# BrainA2-A-11Nov2014.net
KiCad netlist of a schematic drawn in EAGLE
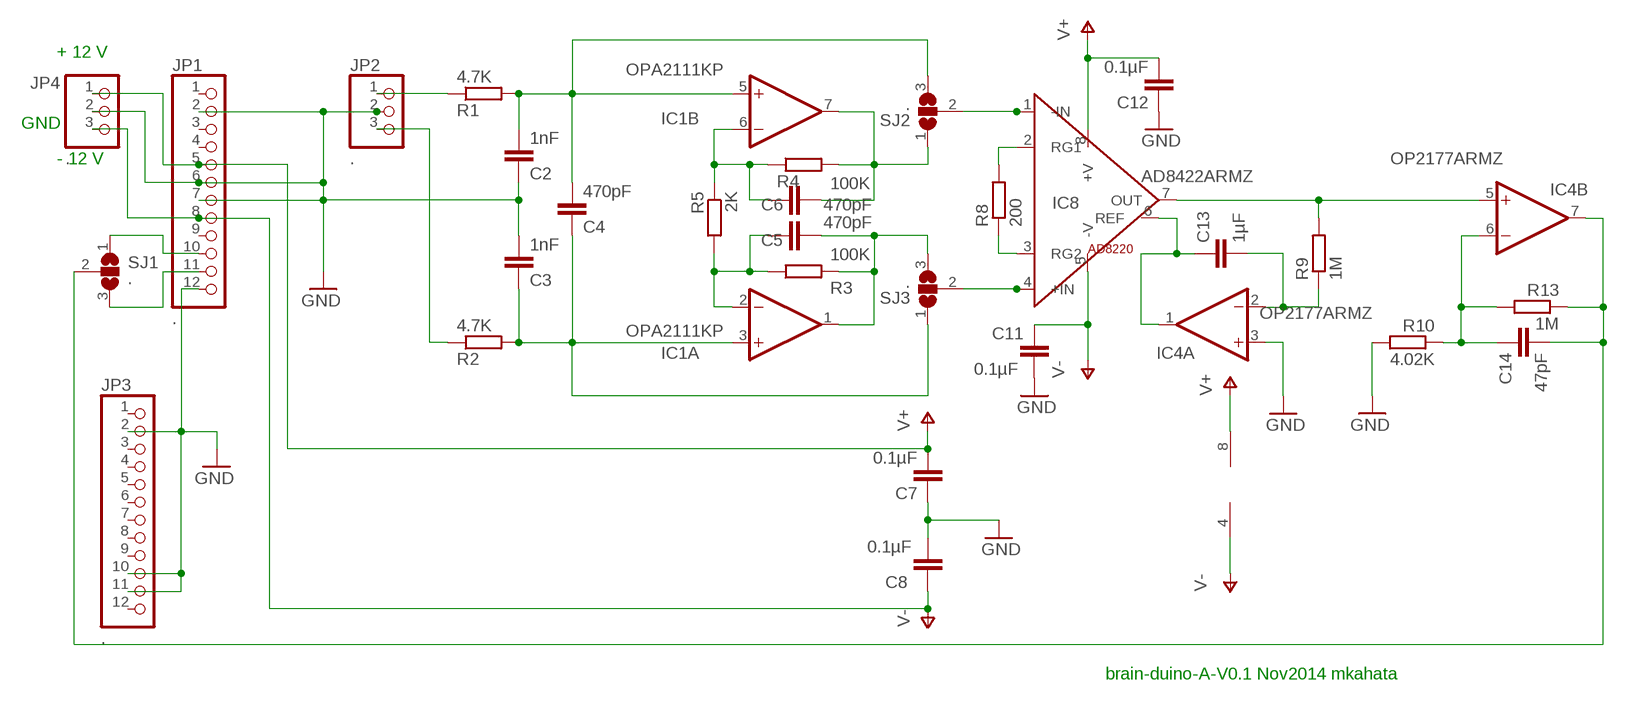
[diagram p0: schematic, sheet 1]

(export (version "E")
  (design (tool "Eeschema 10.0.6"))
  (components
    (comp (ref "C2")
      (value "1nF")
      (footprint "eagle-import:C0603")
      (libsource (lib "eagle-import") (part "C-EUC0603"))
    )
    (comp (ref "C3")
      (value "1nF")
      (footprint "eagle-import:C0603")
      (libsource (lib "eagle-import") (part "C-EUC0603"))
    )
    (comp (ref "C4")
      (value "470pF")
      (footprint "eagle-import:C0603")
      (libsource (lib "eagle-import") (part "C-EUC0603"))
    )
    (comp (ref "C5")
      (value "470pF")
      (footprint "eagle-import:C0603")
      (libsource (lib "eagle-import") (part "C-EUC0603"))
    )
    (comp (ref "C6")
      (value "470pF")
      (footprint "eagle-import:C0603")
      (libsource (lib "eagle-import") (part "C-EUC0603"))
    )
    (comp (ref "C7")
      (value "0.1µF")
      (footprint "eagle-import:C0603")
      (libsource (lib "eagle-import") (part "C-EUC0603"))
    )
    (comp (ref "C8")
      (value "0.1µF")
      (footprint "eagle-import:C0603")
      (libsource (lib "eagle-import") (part "C-EUC0603"))
    )
    (comp (ref "C11")
      (value "0.1µF")
      (footprint "eagle-import:C0603")
      (libsource (lib "eagle-import") (part "C-EUC0603"))
    )
    (comp (ref "C12")
      (value "0.1µF")
      (footprint "eagle-import:C0603")
      (libsource (lib "eagle-import") (part "C-EUC0603"))
    )
    (comp (ref "C13")
      (value "1µF")
      (footprint "eagle-import:C0603")
      (libsource (lib "eagle-import") (part "C-EUC0603"))
    )
    (comp (ref "C14")
      (value "47pF")
      (footprint "eagle-import:C0603")
      (libsource (lib "eagle-import") (part "C-EUC0603"))
    )
    (comp (ref "IC1")
      (value "OPA2111KP")
      (footprint "eagle-import:DIL08")
      (libsource (lib "eagle-import") (part "OPA2111P"))
    )
    (comp (ref "IC4")
      (value "OP2177ARMZ")
      (footprint "eagle-import:MSOP08")
      (libsource (lib "eagle-import") (part "OP1277RM"))
    )
    (comp (ref "IC8")
      (value "AD8422ARMZ")
      (footprint "eagle-import:AD8220")
      (libsource (lib "eagle-import") (part "AD8220"))
    )
    (comp (ref "JP1")
      (value ".")
      (footprint "eagle-import:1X12")
      (libsource (lib "eagle-import") (part "PINHD-1X12"))
    )
    (comp (ref "JP2")
      (value ".")
      (footprint "eagle-import:1X03")
      (libsource (lib "eagle-import") (part "PINHD-1X3"))
    )
    (comp (ref "JP3")
      (value ".")
      (footprint "eagle-import:1X12")
      (libsource (lib "eagle-import") (part "PINHD-1X12"))
    )
    (comp (ref "JP4")
      (value ".")
      (footprint "eagle-import:1X03")
      (libsource (lib "eagle-import") (part "PINHD-1X3"))
    )
    (comp (ref "R1")
      (value "4.7K")
      (footprint "eagle-import:R0603")
      (libsource (lib "eagle-import") (part "R-EU_R0603"))
    )
    (comp (ref "R2")
      (value "4.7K")
      (footprint "eagle-import:R0603")
      (libsource (lib "eagle-import") (part "R-EU_R0603"))
    )
    (comp (ref "R3")
      (value "100K")
      (footprint "eagle-import:R0603")
      (libsource (lib "eagle-import") (part "R-EU_R0603"))
    )
    (comp (ref "R4")
      (value "100K")
      (footprint "eagle-import:R0603")
      (libsource (lib "eagle-import") (part "R-EU_R0603"))
    )
    (comp (ref "R5")
      (value "2K")
      (footprint "eagle-import:R0603")
      (libsource (lib "eagle-import") (part "R-EU_R0603"))
    )
    (comp (ref "R8")
      (value "200")
      (footprint "eagle-import:R0603")
      (libsource (lib "eagle-import") (part "R-EU_R0603"))
    )
    (comp (ref "R9")
      (value "1M")
      (footprint "eagle-import:R0603")
      (libsource (lib "eagle-import") (part "R-EU_R0603"))
    )
    (comp (ref "R10")
      (value "4.02K")
      (footprint "eagle-import:R0603")
      (libsource (lib "eagle-import") (part "R-EU_R0603"))
    )
    (comp (ref "R13")
      (value "1M")
      (footprint "eagle-import:R0603")
      (libsource (lib "eagle-import") (part "R-EU_R0603"))
    )
    (comp (ref "SJ1")
      (value ".")
      (footprint "eagle-import:SJ_2")
      (libsource (lib "eagle-import") (part "SJ2W"))
    )
    (comp (ref "SJ2")
      (value ".")
      (footprint "eagle-import:SJ_2")
      (libsource (lib "eagle-import") (part "SJ2W"))
    )
    (comp (ref "SJ3")
      (value ".")
      (footprint "eagle-import:SJ_2")
      (libsource (lib "eagle-import") (part "SJ2W"))
    )
  )
  (nets
    (net (code "1") (name "GND") (class "Default")
      (node (ref "C11") (pin "2") (pinfunction "2_2") (pintype "passive"))
      (node (ref "C12") (pin "1") (pinfunction "1_1") (pintype "passive"))
      (node (ref "C2") (pin "1") (pinfunction "1_1") (pintype "passive"))
      (node (ref "C3") (pin "2") (pinfunction "2_2") (pintype "passive"))
      (node (ref "C7") (pin "1") (pinfunction "1_1") (pintype "passive"))
      (node (ref "C8") (pin "2") (pinfunction "2_2") (pintype "passive"))
      (node (ref "IC4") (pin "3") (pinfunction "+IN_3") (pintype "input"))
      (node (ref "JP1") (pin "12") (pinfunction "12_12") (pintype "passive"))
      (node (ref "JP1") (pin "2") (pinfunction "2_2") (pintype "passive"))
      (node (ref "JP1") (pin "6") (pinfunction "6_6") (pintype "passive"))
      (node (ref "JP1") (pin "7") (pinfunction "7_7") (pintype "passive"))
      (node (ref "JP2") (pin "2") (pinfunction "2_2") (pintype "passive"))
      (node (ref "JP3") (pin "10") (pinfunction "10_10") (pintype "passive"))
      (node (ref "JP3") (pin "11") (pinfunction "11_11") (pintype "passive"))
      (node (ref "JP3") (pin "2") (pinfunction "2_2") (pintype "passive"))
      (node (ref "JP4") (pin "2") (pinfunction "2_2") (pintype "passive"))
      (node (ref "R10") (pin "2") (pinfunction "2_2") (pintype "passive"))
    )
    (net (code "2") (name "Net-(IC1A-+IN)") (class "Default")
      (node (ref "C3") (pin "1") (pinfunction "1_1") (pintype "passive"))
      (node (ref "C4") (pin "1") (pinfunction "1_1") (pintype "passive"))
      (node (ref "IC1") (pin "3") (pinfunction "+IN_3") (pintype "input"))
      (node (ref "R2") (pin "2") (pinfunction "2_2") (pintype "passive"))
      (node (ref "SJ3") (pin "1") (pinfunction "1_1") (pintype "passive"))
    )
    (net (code "3") (name "Net-(IC1A--IN)") (class "Default")
      (node (ref "C5") (pin "1") (pinfunction "1_1") (pintype "passive"))
      (node (ref "IC1") (pin "2") (pinfunction "-IN_2") (pintype "input"))
      (node (ref "R3") (pin "1") (pinfunction "1_1") (pintype "passive"))
      (node (ref "R5") (pin "2") (pinfunction "2_2") (pintype "passive"))
    )
    (net (code "4") (name "Net-(IC1A-OUT)") (class "Default")
      (node (ref "C5") (pin "2") (pinfunction "2_2") (pintype "passive"))
      (node (ref "IC1") (pin "1") (pinfunction "OUT_1") (pintype "output"))
      (node (ref "R3") (pin "2") (pinfunction "2_2") (pintype "passive"))
      (node (ref "SJ3") (pin "3") (pinfunction "3_3") (pintype "passive"))
    )
    (net (code "5") (name "Net-(IC1B-+IN)") (class "Default")
      (node (ref "C2") (pin "2") (pinfunction "2_2") (pintype "passive"))
      (node (ref "C4") (pin "2") (pinfunction "2_2") (pintype "passive"))
      (node (ref "IC1") (pin "5") (pinfunction "+IN_5") (pintype "input"))
      (node (ref "R1") (pin "2") (pinfunction "2_2") (pintype "passive"))
      (node (ref "SJ2") (pin "3") (pinfunction "3_3") (pintype "passive"))
    )
    (net (code "6") (name "Net-(IC1B--IN)") (class "Default")
      (node (ref "C6") (pin "1") (pinfunction "1_1") (pintype "passive"))
      (node (ref "IC1") (pin "6") (pinfunction "-IN_6") (pintype "input"))
      (node (ref "R4") (pin "1") (pinfunction "1_1") (pintype "passive"))
      (node (ref "R5") (pin "1") (pinfunction "1_1") (pintype "passive"))
    )
    (net (code "7") (name "Net-(IC1B-OUT)") (class "Default")
      (node (ref "C6") (pin "2") (pinfunction "2_2") (pintype "passive"))
      (node (ref "IC1") (pin "7") (pinfunction "OUT_7") (pintype "output"))
      (node (ref "R4") (pin "2") (pinfunction "2_2") (pintype "passive"))
      (node (ref "SJ2") (pin "1") (pinfunction "1_1") (pintype "passive"))
    )
    (net (code "8") (name "Net-(IC4A--IN)") (class "Default")
      (node (ref "C13") (pin "2") (pinfunction "2_2") (pintype "passive"))
      (node (ref "IC4") (pin "2") (pinfunction "-IN_2") (pintype "input"))
      (node (ref "R9") (pin "1") (pinfunction "1_1") (pintype "passive"))
    )
    (net (code "9") (name "Net-(IC4A-OUT)") (class "Default")
      (node (ref "C13") (pin "1") (pinfunction "1_1") (pintype "passive"))
      (node (ref "IC4") (pin "1") (pinfunction "OUT_1") (pintype "output"))
      (node (ref "IC8") (pin "6") (pinfunction "REF_6") (pintype "input"))
    )
    (net (code "10") (name "Net-(IC4B-+IN)") (class "Default")
      (node (ref "IC4") (pin "5") (pinfunction "+IN_5") (pintype "input"))
      (node (ref "IC8") (pin "7") (pinfunction "OUT_7") (pintype "input"))
      (node (ref "R9") (pin "2") (pinfunction "2_2") (pintype "passive"))
    )
    (net (code "11") (name "Net-(IC4B--IN)") (class "Default")
      (node (ref "C14") (pin "1") (pinfunction "1_1") (pintype "passive"))
      (node (ref "IC4") (pin "6") (pinfunction "-IN_6") (pintype "input"))
      (node (ref "R10") (pin "1") (pinfunction "1_1") (pintype "passive"))
      (node (ref "R13") (pin "2") (pinfunction "2_2") (pintype "passive"))
    )
    (net (code "12") (name "Net-(IC4B-OUT)") (class "Default")
      (node (ref "C14") (pin "2") (pinfunction "2_2") (pintype "passive"))
      (node (ref "IC4") (pin "7") (pinfunction "OUT_7") (pintype "output"))
      (node (ref "R13") (pin "1") (pinfunction "1_1") (pintype "passive"))
      (node (ref "SJ1") (pin "2") (pinfunction "2_2") (pintype "passive"))
    )
    (net (code "13") (name "Net-(IC8-+IN)") (class "Default")
      (node (ref "IC8") (pin "4") (pinfunction "+IN_4") (pintype "passive"))
      (node (ref "SJ3") (pin "2") (pinfunction "2_2") (pintype "passive"))
    )
    (net (code "14") (name "Net-(IC8--IN)") (class "Default")
      (node (ref "IC8") (pin "1") (pinfunction "-IN_1") (pintype "input"))
      (node (ref "SJ2") (pin "2") (pinfunction "2_2") (pintype "passive"))
    )
    (net (code "15") (name "Net-(IC8-RG1)") (class "Default")
      (node (ref "IC8") (pin "2") (pinfunction "RG1_2") (pintype "input"))
      (node (ref "R8") (pin "2") (pinfunction "2_2") (pintype "passive"))
    )
    (net (code "16") (name "Net-(IC8-RG2)") (class "Default")
      (node (ref "IC8") (pin "3") (pinfunction "RG2_3") (pintype "input"))
      (node (ref "R8") (pin "1") (pinfunction "1_1") (pintype "passive"))
    )
    (net (code "17") (name "Net-(JP1-Pad10)") (class "Default")
      (node (ref "JP1") (pin "10") (pinfunction "10_10") (pintype "passive"))
      (node (ref "SJ1") (pin "1") (pinfunction "1_1") (pintype "passive"))
    )
    (net (code "18") (name "Net-(JP1-Pad11)") (class "Default")
      (node (ref "JP1") (pin "11") (pinfunction "11_11") (pintype "passive"))
      (node (ref "SJ1") (pin "3") (pinfunction "3_3") (pintype "passive"))
    )
    (net (code "19") (name "Net-(JP2-Pad1)") (class "Default")
      (node (ref "JP2") (pin "1") (pinfunction "1_1") (pintype "passive"))
      (node (ref "R1") (pin "1") (pinfunction "1_1") (pintype "passive"))
    )
    (net (code "20") (name "Net-(JP2-Pad3)") (class "Default")
      (node (ref "JP2") (pin "3") (pinfunction "3_3") (pintype "passive"))
      (node (ref "R2") (pin "1") (pinfunction "1_1") (pintype "passive"))
    )
    (net (code "21") (name "V+") (class "Default")
      (node (ref "C12") (pin "2") (pinfunction "2_2") (pintype "passive"))
      (node (ref "C7") (pin "2") (pinfunction "2_2") (pintype "passive"))
      (node (ref "IC4") (pin "8") (pinfunction "V+_8") (pintype "power_in"))
      (node (ref "IC8") (pin "8") (pinfunction "+V_8") (pintype "power_in"))
      (node (ref "JP1") (pin "5") (pinfunction "5_5") (pintype "passive"))
      (node (ref "JP4") (pin "1") (pinfunction "1_1") (pintype "passive"))
    )
    (net (code "22") (name "V-") (class "Default")
      (node (ref "C11") (pin "1") (pinfunction "1_1") (pintype "passive"))
      (node (ref "C8") (pin "1") (pinfunction "1_1") (pintype "passive"))
      (node (ref "IC4") (pin "4") (pinfunction "V-_4") (pintype "power_in"))
      (node (ref "IC8") (pin "5") (pinfunction "-V_5") (pintype "power_in"))
      (node (ref "JP1") (pin "8") (pinfunction "8_8") (pintype "passive"))
      (node (ref "JP4") (pin "3") (pinfunction "3_3") (pintype "passive"))
    )
    (net (code "23") (name "unconnected-(JP1-Pad1)") (class "Default")
      (node (ref "JP1") (pin "1") (pinfunction "1_1") (pintype "passive"))
    )
    (net (code "24") (name "unconnected-(JP1-Pad3)") (class "Default")
      (node (ref "JP1") (pin "3") (pinfunction "3_3") (pintype "passive"))
    )
    (net (code "25") (name "unconnected-(JP1-Pad4)") (class "Default")
      (node (ref "JP1") (pin "4") (pinfunction "4_4") (pintype "passive"))
    )
    (net (code "26") (name "unconnected-(JP1-Pad9)") (class "Default")
      (node (ref "JP1") (pin "9") (pinfunction "9_9") (pintype "passive"))
    )
    (net (code "27") (name "unconnected-(JP3-Pad1)") (class "Default")
      (node (ref "JP3") (pin "1") (pinfunction "1_1") (pintype "passive"))
    )
    (net (code "28") (name "unconnected-(JP3-Pad3)") (class "Default")
      (node (ref "JP3") (pin "3") (pinfunction "3_3") (pintype "passive"))
    )
    (net (code "29") (name "unconnected-(JP3-Pad4)") (class "Default")
      (node (ref "JP3") (pin "4") (pinfunction "4_4") (pintype "passive"))
    )
    (net (code "30") (name "unconnected-(JP3-Pad5)") (class "Default")
      (node (ref "JP3") (pin "5") (pinfunction "5_5") (pintype "passive"))
    )
    (net (code "31") (name "unconnected-(JP3-Pad6)") (class "Default")
      (node (ref "JP3") (pin "6") (pinfunction "6_6") (pintype "passive"))
    )
    (net (code "32") (name "unconnected-(JP3-Pad7)") (class "Default")
      (node (ref "JP3") (pin "7") (pinfunction "7_7") (pintype "passive"))
    )
    (net (code "33") (name "unconnected-(JP3-Pad8)") (class "Default")
      (node (ref "JP3") (pin "8") (pinfunction "8_8") (pintype "passive"))
    )
    (net (code "34") (name "unconnected-(JP3-Pad9)") (class "Default")
      (node (ref "JP3") (pin "9") (pinfunction "9_9") (pintype "passive"))
    )
    (net (code "35") (name "unconnected-(JP3-Pad12)") (class "Default")
      (node (ref "JP3") (pin "12") (pinfunction "12_12") (pintype "passive"))
    )
  )
)
